# ProPrj__-__2025-12-04.net
KiCad netlist of a schematic drawn in EasyEDA Pro
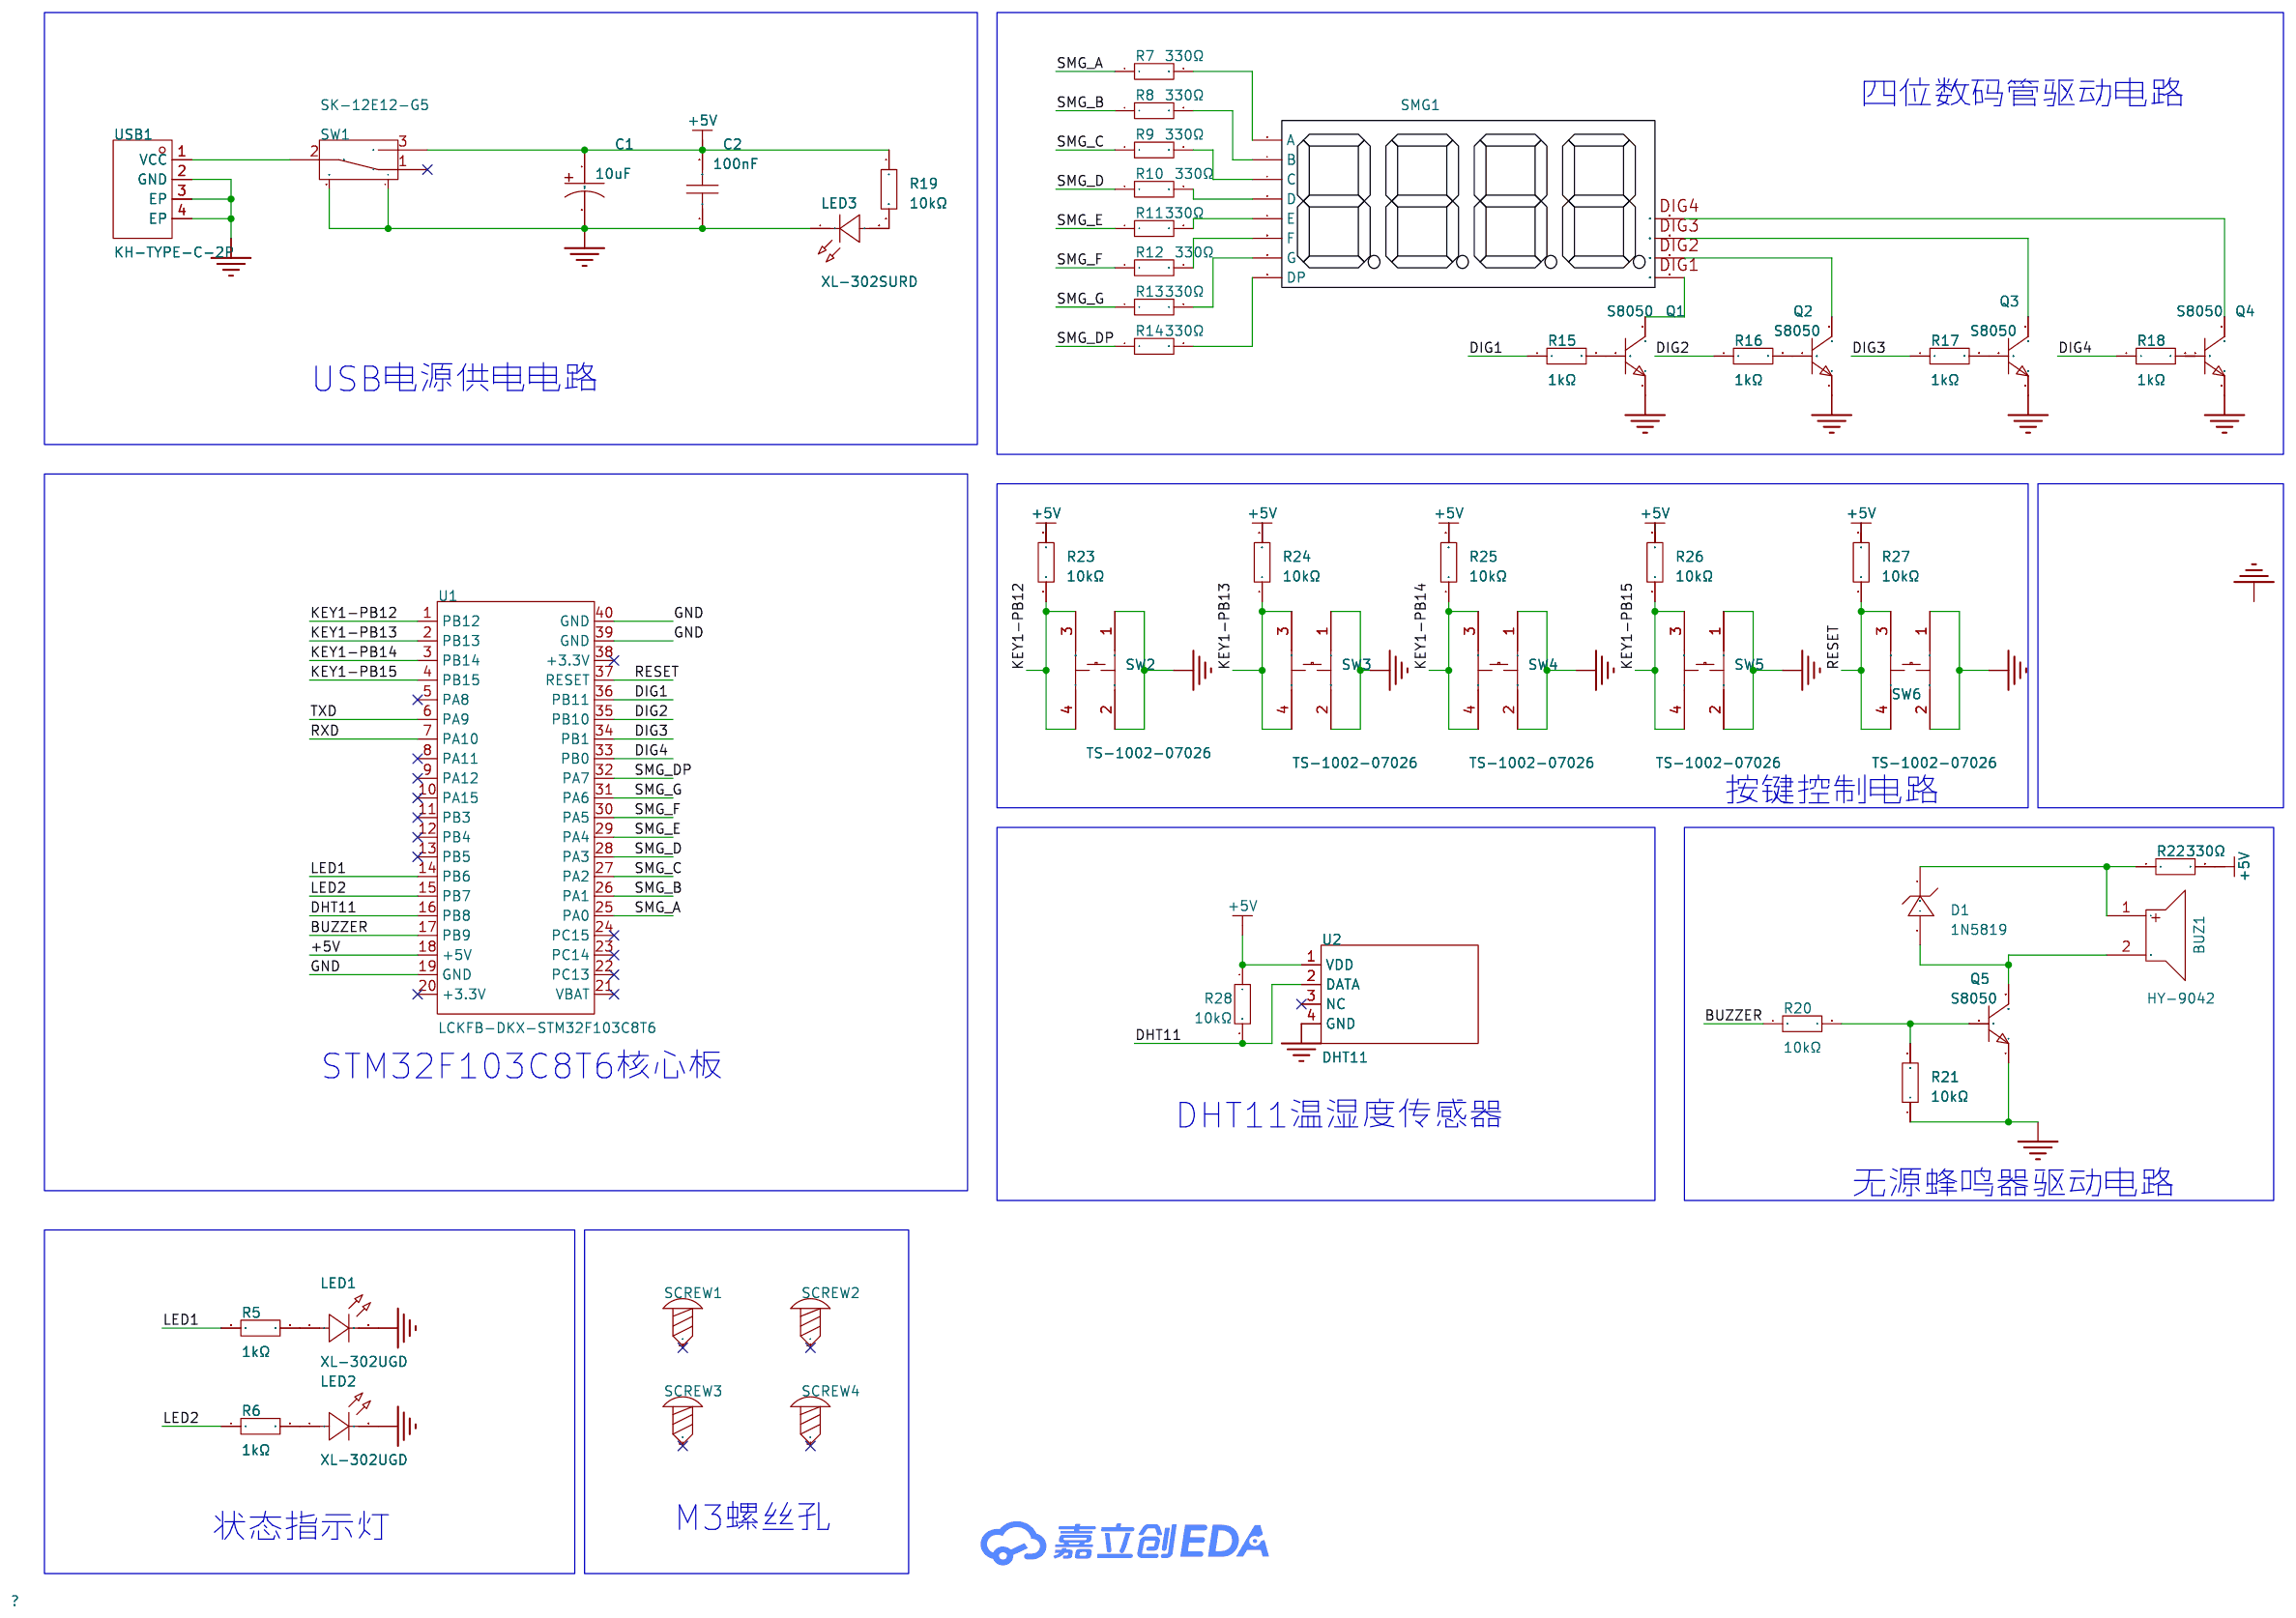
[diagram p0: schematic sheet]

(export (version "E")
  (design (tool "Eeschema 10.0.6"))
  (components
    (comp (ref "BUZ1")
      (value "HY-9042")
      (footprint "easyedapro:BUZ-TH_BD9.0-P4.00-D0.6-FD")
      (libsource (lib "easyedapro") (part "HY-9042"))
    )
    (comp (ref "C1")
      (value "10uF")
      (footprint "easyedapro:CAP-TH_BD4.0-P1.50-D0.8-FD")
      (description "容值:10uF;精度:±20%;额定电压:25V;")
      (fields
        (field (name "Manufacturer Part") "KF1E100MB050A00CV0")
        (field (name "Manufacturer") "HUAWEI(华威集团)")
      )
      (libsource (lib "easyedapro") (part "KF1E100MB050A00CV0"))
    )
    (comp (ref "C2")
      (value "100nF")
      (footprint "easyedapro:CAP-TH_L5.0-W2.5-P5.08-D0.7")
      (description "容值:100nF;精度:-20%~+80%;额定电压:50V;温度系数:Y5V;")
      (fields
        (field (name "Manufacturer Part") "CC1H104ZC74D3F5O30MN")
        (field (name "Manufacturer") "Dersonic(德尔创)")
      )
      (libsource (lib "easyedapro") (part "CC1H104ZC74D3F5O30MN"))
    )
    (comp (ref "D1")
      (value "1N5819")
      (footprint "easyedapro:DO-41_BD2.4-L4.7-P8.70-D0.9-RD")
      (description "二极管配置:独立式;正向压降(Vf):900mV@3A;直流反向耐压(Vr):40V;整流电流:1A;")
      (fields (field (name "Manufacturer") "LGE(鲁光)"))
      (libsource (lib "easyedapro") (part "1N5819_C402218"))
    )
    (comp (ref "LED1")
      (value "XL-302UGD")
      (footprint "easyedapro:LED-TH_BD3.8-P2.54-FD_GREEN")
      (fields (field (name "Manufacturer") "XINGLIGHT(成兴光)"))
      (libsource (lib "easyedapro") (part "XL-302UGD"))
    )
    (comp (ref "LED2")
      (value "XL-302UGD")
      (footprint "easyedapro:LED-TH_BD3.8-P2.54-FD_GREEN")
      (fields (field (name "Manufacturer") "XINGLIGHT(成兴光)"))
      (libsource (lib "easyedapro") (part "XL-302UGD"))
    )
    (comp (ref "LED3")
      (value "XL-302SURD")
      (footprint "easyedapro:LED-TH_BD3.8-P2.54-RD")
      (fields (field (name "Manufacturer") "XINGLIGHT(成兴光)"))
      (libsource (lib "easyedapro") (part "XL-302SURD"))
    )
    (comp (ref "Q1")
      (value "S8050")
      (footprint "easyedapro:TO-92-3_L4.5-W3.5-P1.27-L")
      (description "晶体管类型:NPN;集电极电流(Ic):500mA;集射极击穿电压(Vceo):25V;耗散功率(Pd):625mW;直流电流增益(hFE):160@50mA,1V;")
      (fields (field (name "Manufacturer") "JSMSEMI(杰盛微)"))
      (libsource (lib "easyedapro") (part "S8050_C2931492"))
    )
    (comp (ref "Q2")
      (value "S8050")
      (footprint "easyedapro:TO-92-3_L4.5-W3.5-P1.27-L")
      (description "晶体管类型:NPN;集电极电流(Ic):500mA;集射极击穿电压(Vceo):25V;耗散功率(Pd):625mW;直流电流增益(hFE):160@50mA,1V;")
      (fields (field (name "Manufacturer") "JSMSEMI(杰盛微)"))
      (libsource (lib "easyedapro") (part "S8050_C2931492"))
    )
    (comp (ref "Q3")
      (value "S8050")
      (footprint "easyedapro:TO-92-3_L4.5-W3.5-P1.27-L")
      (description "晶体管类型:NPN;集电极电流(Ic):500mA;集射极击穿电压(Vceo):25V;耗散功率(Pd):625mW;直流电流增益(hFE):160@50mA,1V;")
      (fields (field (name "Manufacturer") "JSMSEMI(杰盛微)"))
      (libsource (lib "easyedapro") (part "S8050_C2931492"))
    )
    (comp (ref "Q4")
      (value "S8050")
      (footprint "easyedapro:TO-92-3_L4.5-W3.5-P1.27-L")
      (description "晶体管类型:NPN;集电极电流(Ic):500mA;集射极击穿电压(Vceo):25V;耗散功率(Pd):625mW;直流电流增益(hFE):160@50mA,1V;")
      (fields (field (name "Manufacturer") "JSMSEMI(杰盛微)"))
      (libsource (lib "easyedapro") (part "S8050_C2931492"))
    )
    (comp (ref "Q5")
      (value "S8050")
      (footprint "easyedapro:TO-92-3_L4.5-W3.5-P1.27-L")
      (description "晶体管类型:NPN;集电极电流(Ic):500mA;集射极击穿电压(Vceo):25V;耗散功率(Pd):625mW;直流电流增益(hFE):160@50mA,1V;")
      (fields (field (name "Manufacturer") "JSMSEMI(杰盛微)"))
      (libsource (lib "easyedapro") (part "S8050_C2931492"))
    )
    (comp (ref "R5")
      (value "1kΩ")
      (footprint "easyedapro:RES-TH_BD2.2-L6.5-P10.50-D0.6")
      (description "电阻类型:金属膜电阻;阻值:1kΩ;精度:±5%;功率:250mW;")
      (fields (field (name "Manufacturer Part") "MFR-25JT-52-1K") (field (name "Manufacturer") "YAGEO(国巨)"))
      (libsource (lib "easyedapro") (part "MFR-25JT-52-1K"))
    )
    (comp (ref "R6")
      (value "1kΩ")
      (footprint "easyedapro:RES-TH_BD2.2-L6.5-P10.50-D0.6")
      (description "电阻类型:金属膜电阻;阻值:1kΩ;精度:±5%;功率:250mW;")
      (fields (field (name "Manufacturer Part") "MFR-25JT-52-1K") (field (name "Manufacturer") "YAGEO(国巨)"))
      (libsource (lib "easyedapro") (part "MFR-25JT-52-1K"))
    )
    (comp (ref "R7")
      (value "330Ω")
      (footprint "easyedapro:RES-TH_BD2.2-L6.5-P10.50-D0.6")
      (description "电阻类型:金属膜电阻;阻值:330Ω;精度:±1%;功率:250mW;温度系数:±50ppm/°C;")
      (fields (field (name "Manufacturer Part") "MFR-25FTE52-330R") (field (name "Manufacturer") "YAGEO(国巨)"))
      (libsource (lib "easyedapro") (part "MFR-25FTE52-330R"))
    )
    (comp (ref "R8")
      (value "330Ω")
      (footprint "easyedapro:RES-TH_BD2.2-L6.5-P10.50-D0.6")
      (description "电阻类型:金属膜电阻;阻值:330Ω;精度:±1%;功率:250mW;温度系数:±50ppm/°C;")
      (fields (field (name "Manufacturer Part") "MFR-25FTE52-330R") (field (name "Manufacturer") "YAGEO(国巨)"))
      (libsource (lib "easyedapro") (part "MFR-25FTE52-330R"))
    )
    (comp (ref "R9")
      (value "330Ω")
      (footprint "easyedapro:RES-TH_BD2.2-L6.5-P10.50-D0.6")
      (description "电阻类型:金属膜电阻;阻值:330Ω;精度:±1%;功率:250mW;温度系数:±50ppm/°C;")
      (fields (field (name "Manufacturer Part") "MFR-25FTE52-330R") (field (name "Manufacturer") "YAGEO(国巨)"))
      (libsource (lib "easyedapro") (part "MFR-25FTE52-330R"))
    )
    (comp (ref "R10")
      (value "330Ω")
      (footprint "easyedapro:RES-TH_BD2.2-L6.5-P10.50-D0.6")
      (description "电阻类型:金属膜电阻;阻值:330Ω;精度:±1%;功率:250mW;温度系数:±50ppm/°C;")
      (fields (field (name "Manufacturer Part") "MFR-25FTE52-330R") (field (name "Manufacturer") "YAGEO(国巨)"))
      (libsource (lib "easyedapro") (part "MFR-25FTE52-330R"))
    )
    (comp (ref "R11")
      (value "330Ω")
      (footprint "easyedapro:RES-TH_BD2.2-L6.5-P10.50-D0.6")
      (description "电阻类型:金属膜电阻;阻值:330Ω;精度:±1%;功率:250mW;温度系数:±50ppm/°C;")
      (fields (field (name "Manufacturer Part") "MFR-25FTE52-330R") (field (name "Manufacturer") "YAGEO(国巨)"))
      (libsource (lib "easyedapro") (part "MFR-25FTE52-330R"))
    )
    (comp (ref "R12")
      (value "330Ω")
      (footprint "easyedapro:RES-TH_BD2.2-L6.5-P10.50-D0.6")
      (description "电阻类型:金属膜电阻;阻值:330Ω;精度:±1%;功率:250mW;温度系数:±50ppm/°C;")
      (fields (field (name "Manufacturer Part") "MFR-25FTE52-330R") (field (name "Manufacturer") "YAGEO(国巨)"))
      (libsource (lib "easyedapro") (part "MFR-25FTE52-330R"))
    )
    (comp (ref "R13")
      (value "330Ω")
      (footprint "easyedapro:RES-TH_BD2.2-L6.5-P10.50-D0.6")
      (description "电阻类型:金属膜电阻;阻值:330Ω;精度:±1%;功率:250mW;温度系数:±50ppm/°C;")
      (fields (field (name "Manufacturer Part") "MFR-25FTE52-330R") (field (name "Manufacturer") "YAGEO(国巨)"))
      (libsource (lib "easyedapro") (part "MFR-25FTE52-330R"))
    )
    (comp (ref "R14")
      (value "330Ω")
      (footprint "easyedapro:RES-TH_BD2.2-L6.5-P10.50-D0.6")
      (description "电阻类型:金属膜电阻;阻值:330Ω;精度:±1%;功率:250mW;温度系数:±50ppm/°C;")
      (fields (field (name "Manufacturer Part") "MFR-25FTE52-330R") (field (name "Manufacturer") "YAGEO(国巨)"))
      (libsource (lib "easyedapro") (part "MFR-25FTE52-330R"))
    )
    (comp (ref "R15")
      (value "1kΩ")
      (footprint "easyedapro:RES-TH_BD2.2-L6.5-P10.50-D0.6")
      (description "电阻类型:金属膜电阻;阻值:1kΩ;精度:±5%;功率:250mW;")
      (fields (field (name "Manufacturer Part") "MFR-25JT-52-1K") (field (name "Manufacturer") "YAGEO(国巨)"))
      (libsource (lib "easyedapro") (part "MFR-25JT-52-1K"))
    )
    (comp (ref "R16")
      (value "1kΩ")
      (footprint "easyedapro:RES-TH_BD2.2-L6.5-P10.50-D0.6")
      (description "电阻类型:金属膜电阻;阻值:1kΩ;精度:±5%;功率:250mW;")
      (fields (field (name "Manufacturer Part") "MFR-25JT-52-1K") (field (name "Manufacturer") "YAGEO(国巨)"))
      (libsource (lib "easyedapro") (part "MFR-25JT-52-1K"))
    )
    (comp (ref "R17")
      (value "1kΩ")
      (footprint "easyedapro:RES-TH_BD2.2-L6.5-P10.50-D0.6")
      (description "电阻类型:金属膜电阻;阻值:1kΩ;精度:±5%;功率:250mW;")
      (fields (field (name "Manufacturer Part") "MFR-25JT-52-1K") (field (name "Manufacturer") "YAGEO(国巨)"))
      (libsource (lib "easyedapro") (part "MFR-25JT-52-1K"))
    )
    (comp (ref "R18")
      (value "1kΩ")
      (footprint "easyedapro:RES-TH_BD2.2-L6.5-P10.50-D0.6")
      (description "电阻类型:金属膜电阻;阻值:1kΩ;精度:±5%;功率:250mW;")
      (fields (field (name "Manufacturer Part") "MFR-25JT-52-1K") (field (name "Manufacturer") "YAGEO(国巨)"))
      (libsource (lib "easyedapro") (part "MFR-25JT-52-1K"))
    )
    (comp (ref "R19")
      (value "10kΩ")
      (footprint "easyedapro:RES-TH_BD2.4-L6.3-P10.30-D0.6")
      (description "电阻类型:金属膜电阻;阻值:10kΩ;精度:±5%;功率:250mW;")
      (fields (field (name "Manufacturer Part") "MFR-25JT-52-10K") (field (name "Manufacturer") "YAGEO(国巨)"))
      (libsource (lib "easyedapro") (part "MFR-25JT-52-10K"))
    )
    (comp (ref "R20")
      (value "10kΩ")
      (footprint "easyedapro:RES-TH_BD2.4-L6.3-P10.30-D0.6")
      (description "电阻类型:金属膜电阻;阻值:10kΩ;精度:±5%;功率:250mW;")
      (fields (field (name "Manufacturer Part") "MFR-25JT-52-10K") (field (name "Manufacturer") "YAGEO(国巨)"))
      (libsource (lib "easyedapro") (part "MFR-25JT-52-10K"))
    )
    (comp (ref "R21")
      (value "10kΩ")
      (footprint "easyedapro:RES-TH_BD2.4-L6.3-P10.30-D0.6")
      (description "电阻类型:金属膜电阻;阻值:10kΩ;精度:±5%;功率:250mW;")
      (fields (field (name "Manufacturer Part") "MFR-25JT-52-10K") (field (name "Manufacturer") "YAGEO(国巨)"))
      (libsource (lib "easyedapro") (part "MFR-25JT-52-10K"))
    )
    (comp (ref "R22")
      (value "330Ω")
      (footprint "easyedapro:RES-TH_BD2.2-L6.5-P10.50-D0.6")
      (description "电阻类型:金属膜电阻;阻值:330Ω;精度:±1%;功率:250mW;温度系数:±50ppm/°C;")
      (fields (field (name "Manufacturer Part") "MFR-25FTE52-330R") (field (name "Manufacturer") "YAGEO(国巨)"))
      (libsource (lib "easyedapro") (part "MFR-25FTE52-330R"))
    )
    (comp (ref "R23")
      (value "10kΩ")
      (footprint "easyedapro:RES-TH_BD2.4-L6.3-P10.30-D0.6")
      (description "电阻类型:金属膜电阻;阻值:10kΩ;精度:±5%;功率:250mW;")
      (fields (field (name "Manufacturer Part") "MFR-25JT-52-10K") (field (name "Manufacturer") "YAGEO(国巨)"))
      (libsource (lib "easyedapro") (part "MFR-25JT-52-10K"))
    )
    (comp (ref "R24")
      (value "10kΩ")
      (footprint "easyedapro:RES-TH_BD2.4-L6.3-P10.30-D0.6")
      (description "电阻类型:金属膜电阻;阻值:10kΩ;精度:±5%;功率:250mW;")
      (fields (field (name "Manufacturer Part") "MFR-25JT-52-10K") (field (name "Manufacturer") "YAGEO(国巨)"))
      (libsource (lib "easyedapro") (part "MFR-25JT-52-10K"))
    )
    (comp (ref "R25")
      (value "10kΩ")
      (footprint "easyedapro:RES-TH_BD2.4-L6.3-P10.30-D0.6")
      (description "电阻类型:金属膜电阻;阻值:10kΩ;精度:±5%;功率:250mW;")
      (fields (field (name "Manufacturer Part") "MFR-25JT-52-10K") (field (name "Manufacturer") "YAGEO(国巨)"))
      (libsource (lib "easyedapro") (part "MFR-25JT-52-10K"))
    )
    (comp (ref "R26")
      (value "10kΩ")
      (footprint "easyedapro:RES-TH_BD2.4-L6.3-P10.30-D0.6")
      (description "电阻类型:金属膜电阻;阻值:10kΩ;精度:±5%;功率:250mW;")
      (fields (field (name "Manufacturer Part") "MFR-25JT-52-10K") (field (name "Manufacturer") "YAGEO(国巨)"))
      (libsource (lib "easyedapro") (part "MFR-25JT-52-10K"))
    )
    (comp (ref "R27")
      (value "10kΩ")
      (footprint "easyedapro:RES-TH_BD2.4-L6.3-P10.30-D0.6")
      (description "电阻类型:金属膜电阻;阻值:10kΩ;精度:±5%;功率:250mW;")
      (fields (field (name "Manufacturer Part") "MFR-25JT-52-10K") (field (name "Manufacturer") "YAGEO(国巨)"))
      (libsource (lib "easyedapro") (part "MFR-25JT-52-10K"))
    )
    (comp (ref "R28")
      (value "10kΩ")
      (footprint "easyedapro:RES-TH_BD2.4-L6.3-P10.30-D0.6")
      (description "电阻类型:金属膜电阻;阻值:10kΩ;精度:±5%;功率:250mW;")
      (fields (field (name "Manufacturer Part") "MFR-25JT-52-10K") (field (name "Manufacturer") "YAGEO(国巨)"))
      (libsource (lib "easyedapro") (part "MFR-25JT-52-10K"))
    )
    (comp (ref "SCREW1")
      (value "~")
      (footprint "easyedapro:M3螺丝")
      (libsource (lib "easyedapro") (part "螺丝孔"))
    )
    (comp (ref "SCREW2")
      (value "~")
      (footprint "easyedapro:M3螺丝")
      (libsource (lib "easyedapro") (part "螺丝孔"))
    )
    (comp (ref "SCREW3")
      (value "~")
      (footprint "easyedapro:M3螺丝")
      (libsource (lib "easyedapro") (part "螺丝孔"))
    )
    (comp (ref "SCREW4")
      (value "~")
      (footprint "easyedapro:M3螺丝")
      (libsource (lib "easyedapro") (part "螺丝孔"))
    )
    (comp (ref "SMG1")
      (value "~")
      (footprint "easyedapro:LED-SEG-TH_FJ5461AH")
      (libsource (lib "easyedapro") (part "LED_SEG_TH_0.56x4"))
    )
    (comp (ref "SW1")
      (value "SK-12E12-G5")
      (footprint "easyedapro:SW-TH_SK-12E12-G5")
      (description "电路结构:单刀双掷;安装方式:-;额定电流:-;额定电压:-;工作寿命:5千次;")
      (fields (field (name "Manufacturer") "韩国韩荣"))
      (libsource (lib "easyedapro") (part "SK-12E12-G5"))
    )
    (comp (ref "SW2")
      (value "TS-1002-07026")
      (footprint "easyedapro:SW-TH_4P-L6.0-W6.0-P4.50-LS6.5")
      (description "电路结构:单刀单掷;按钮形状:圆形按钮;安装方式:直插;开关长度:6mm;开关宽度:6mm;开关高度:7mm;触点电流:50mA;额定电压:12V;带灯:-;工作寿命:-;")
      (fields (field (name "Manufacturer") "XUNPU(讯普)"))
      (libsource (lib "easyedapro") (part "TS-1002-07026"))
    )
    (comp (ref "SW3")
      (value "TS-1002-07026")
      (footprint "easyedapro:SW-TH_4P-L6.0-W6.0-P4.50-LS6.5")
      (description "电路结构:单刀单掷;按钮形状:圆形按钮;安装方式:直插;开关长度:6mm;开关宽度:6mm;开关高度:7mm;触点电流:50mA;额定电压:12V;带灯:-;工作寿命:-;")
      (fields (field (name "Manufacturer") "XUNPU(讯普)"))
      (libsource (lib "easyedapro") (part "TS-1002-07026"))
    )
    (comp (ref "SW4")
      (value "TS-1002-07026")
      (footprint "easyedapro:SW-TH_4P-L6.0-W6.0-P4.50-LS6.5")
      (description "电路结构:单刀单掷;按钮形状:圆形按钮;安装方式:直插;开关长度:6mm;开关宽度:6mm;开关高度:7mm;触点电流:50mA;额定电压:12V;带灯:-;工作寿命:-;")
      (fields (field (name "Manufacturer") "XUNPU(讯普)"))
      (libsource (lib "easyedapro") (part "TS-1002-07026"))
    )
    (comp (ref "SW5")
      (value "TS-1002-07026")
      (footprint "easyedapro:SW-TH_4P-L6.0-W6.0-P4.50-LS6.5")
      (description "电路结构:单刀单掷;按钮形状:圆形按钮;安装方式:直插;开关长度:6mm;开关宽度:6mm;开关高度:7mm;触点电流:50mA;额定电压:12V;带灯:-;工作寿命:-;")
      (fields (field (name "Manufacturer") "XUNPU(讯普)"))
      (libsource (lib "easyedapro") (part "TS-1002-07026"))
    )
    (comp (ref "SW6")
      (value "TS-1002-07026")
      (footprint "easyedapro:SW-TH_4P-L6.0-W6.0-P4.50-LS6.5")
      (description "电路结构:单刀单掷;按钮形状:圆形按钮;安装方式:直插;开关长度:6mm;开关宽度:6mm;开关高度:7mm;触点电流:50mA;额定电压:12V;带灯:-;工作寿命:-;")
      (fields (field (name "Manufacturer") "XUNPU(讯普)"))
      (libsource (lib "easyedapro") (part "TS-1002-07026"))
    )
    (comp (ref "U1")
      (value "LCKFB-DKX-STM32F103C8T6")
      (footprint "easyedapro:CONN-TH_L53.3-W22.9_STM32F103C8T6-CARD")
      (fields (field (name "Manufacturer") "立创开发板"))
      (libsource (lib "easyedapro") (part "LCKFB-DKX-STM32F103C8T6"))
    )
    (comp (ref "U2")
      (value "DHT11")
      (footprint "easyedapro:SENSOR-TH_DHT11")
      (description "新款电容式数字温湿度传感器,老款已停产16.1x12.6x5.8mm")
      (fields (field (name "Manufacturer") "广州奥松"))
      (libsource (lib "easyedapro") (part "DHT11"))
    )
    (comp (ref "USB1")
      (value "KH-TYPE-C-2P")
      (footprint "easyedapro:USB-SMD_KH-TYPE-C-2P")
      (description "连接器类型:Type-C;协议标准:-;公母:-;安装方式:-;触点数量:2P;端口数量:-;额定电流 - 电源:-;工作温度:-;")
      (fields (field (name "Manufacturer") "kinghelm(金航标)"))
      (libsource (lib "easyedapro") (part "KH-TYPE-C-2P"))
    )
  )
  (nets
    (net (code "1") (name "+5V") (class "Default")
      (node (ref "C1") (pin "1") (pinfunction "1_1") (pintype "unspecified"))
      (node (ref "C2") (pin "2") (pinfunction "2_2") (pintype "unspecified"))
      (node (ref "R19") (pin "1") (pinfunction "1_1") (pintype "unspecified"))
      (node (ref "R22") (pin "2") (pinfunction "2_2") (pintype "input"))
      (node (ref "R23") (pin "2") (pinfunction "2_2") (pintype "unspecified"))
      (node (ref "R24") (pin "2") (pinfunction "2_2") (pintype "unspecified"))
      (node (ref "R25") (pin "2") (pinfunction "2_2") (pintype "unspecified"))
      (node (ref "R26") (pin "2") (pinfunction "2_2") (pintype "unspecified"))
      (node (ref "R27") (pin "2") (pinfunction "2_2") (pintype "unspecified"))
      (node (ref "R28") (pin "1") (pinfunction "1_1") (pintype "unspecified"))
      (node (ref "SW1") (pin "3") (pinfunction "3_3") (pintype "unspecified"))
      (node (ref "U1") (pin "18") (pinfunction "+5V_18") (pintype "unspecified"))
      (node (ref "U2") (pin "1") (pinfunction "VDD_1") (pintype "unspecified"))
    )
    (net (code "2") (name "/BUZZER") (class "Default")
      (node (ref "R20") (pin "1") (pinfunction "1_1") (pintype "unspecified"))
      (node (ref "U1") (pin "17") (pinfunction "PB9_17") (pintype "unspecified"))
    )
    (net (code "3") (name "/DHT11") (class "Default")
      (node (ref "R28") (pin "2") (pinfunction "2_2") (pintype "unspecified"))
      (node (ref "U1") (pin "16") (pinfunction "PB8_16") (pintype "unspecified"))
      (node (ref "U2") (pin "2") (pinfunction "DATA_2") (pintype "unspecified"))
    )
    (net (code "4") (name "/DIG1") (class "Default")
      (node (ref "R15") (pin "1") (pinfunction "1_1") (pintype "unspecified"))
      (node (ref "U1") (pin "36") (pinfunction "PB11_36") (pintype "unspecified"))
    )
    (net (code "5") (name "/DIG2") (class "Default")
      (node (ref "R16") (pin "1") (pinfunction "1_1") (pintype "unspecified"))
      (node (ref "U1") (pin "35") (pinfunction "PB10_35") (pintype "unspecified"))
    )
    (net (code "6") (name "/DIG3") (class "Default")
      (node (ref "R17") (pin "1") (pinfunction "1_1") (pintype "unspecified"))
      (node (ref "U1") (pin "34") (pinfunction "PB1_34") (pintype "unspecified"))
    )
    (net (code "7") (name "/DIG4") (class "Default")
      (node (ref "R18") (pin "1") (pinfunction "1_1") (pintype "unspecified"))
      (node (ref "U1") (pin "33") (pinfunction "PB0_33") (pintype "unspecified"))
    )
    (net (code "8") (name "/KEY1-PB12") (class "Default")
      (node (ref "R23") (pin "1") (pinfunction "1_1") (pintype "unspecified"))
      (node (ref "SW2") (pin "3") (pinfunction "3_3") (pintype "unspecified"))
      (node (ref "SW2") (pin "4") (pinfunction "4_4") (pintype "unspecified"))
      (node (ref "U1") (pin "1") (pinfunction "PB12_1") (pintype "unspecified"))
    )
    (net (code "9") (name "/KEY1-PB13") (class "Default")
      (node (ref "R24") (pin "1") (pinfunction "1_1") (pintype "unspecified"))
      (node (ref "SW3") (pin "3") (pinfunction "3_3") (pintype "unspecified"))
      (node (ref "SW3") (pin "4") (pinfunction "4_4") (pintype "unspecified"))
      (node (ref "U1") (pin "2") (pinfunction "PB13_2") (pintype "unspecified"))
    )
    (net (code "10") (name "/KEY1-PB14") (class "Default")
      (node (ref "R25") (pin "1") (pinfunction "1_1") (pintype "unspecified"))
      (node (ref "SW4") (pin "3") (pinfunction "3_3") (pintype "unspecified"))
      (node (ref "SW4") (pin "4") (pinfunction "4_4") (pintype "unspecified"))
      (node (ref "U1") (pin "3") (pinfunction "PB14_3") (pintype "unspecified"))
    )
    (net (code "11") (name "/KEY1-PB15") (class "Default")
      (node (ref "R26") (pin "1") (pinfunction "1_1") (pintype "unspecified"))
      (node (ref "SW5") (pin "3") (pinfunction "3_3") (pintype "unspecified"))
      (node (ref "SW5") (pin "4") (pinfunction "4_4") (pintype "unspecified"))
      (node (ref "U1") (pin "4") (pinfunction "PB15_4") (pintype "unspecified"))
    )
    (net (code "12") (name "/LED1") (class "Default")
      (node (ref "R5") (pin "1") (pinfunction "1_1") (pintype "unspecified"))
      (node (ref "U1") (pin "14") (pinfunction "PB6_14") (pintype "unspecified"))
    )
    (net (code "13") (name "/LED2") (class "Default")
      (node (ref "R6") (pin "1") (pinfunction "1_1") (pintype "unspecified"))
      (node (ref "U1") (pin "15") (pinfunction "PB7_15") (pintype "unspecified"))
    )
    (net (code "14") (name "/RESET") (class "Default")
      (node (ref "R27") (pin "1") (pinfunction "1_1") (pintype "unspecified"))
      (node (ref "SW6") (pin "3") (pinfunction "3_3") (pintype "unspecified"))
      (node (ref "SW6") (pin "4") (pinfunction "4_4") (pintype "unspecified"))
      (node (ref "U1") (pin "37") (pinfunction "RESET_37") (pintype "unspecified"))
    )
    (net (code "15") (name "/RXD") (class "Default")
      (node (ref "U1") (pin "7") (pinfunction "PA10_7") (pintype "unspecified"))
    )
    (net (code "16") (name "/SMG_A") (class "Default")
      (node (ref "R7") (pin "1") (pinfunction "1_1") (pintype "input"))
      (node (ref "U1") (pin "25") (pinfunction "PA0_25") (pintype "unspecified"))
    )
    (net (code "17") (name "/SMG_B") (class "Default")
      (node (ref "R8") (pin "1") (pinfunction "1_1") (pintype "input"))
      (node (ref "U1") (pin "26") (pinfunction "PA1_26") (pintype "unspecified"))
    )
    (net (code "18") (name "/SMG_C") (class "Default")
      (node (ref "R9") (pin "1") (pinfunction "1_1") (pintype "input"))
      (node (ref "U1") (pin "27") (pinfunction "PA2_27") (pintype "unspecified"))
    )
    (net (code "19") (name "/SMG_D") (class "Default")
      (node (ref "R10") (pin "1") (pinfunction "1_1") (pintype "input"))
      (node (ref "U1") (pin "28") (pinfunction "PA3_28") (pintype "unspecified"))
    )
    (net (code "20") (name "/SMG_DP") (class "Default")
      (node (ref "R14") (pin "1") (pinfunction "1_1") (pintype "input"))
      (node (ref "U1") (pin "32") (pinfunction "PA7_32") (pintype "unspecified"))
    )
    (net (code "21") (name "/SMG_E") (class "Default")
      (node (ref "R11") (pin "1") (pinfunction "1_1") (pintype "input"))
      (node (ref "U1") (pin "29") (pinfunction "PA4_29") (pintype "unspecified"))
    )
    (net (code "22") (name "/SMG_F") (class "Default")
      (node (ref "R12") (pin "1") (pinfunction "1_1") (pintype "input"))
      (node (ref "U1") (pin "30") (pinfunction "PA5_30") (pintype "unspecified"))
    )
    (net (code "23") (name "/SMG_G") (class "Default")
      (node (ref "R13") (pin "1") (pinfunction "1_1") (pintype "input"))
      (node (ref "U1") (pin "31") (pinfunction "PA6_31") (pintype "unspecified"))
    )
    (net (code "24") (name "/TXD") (class "Default")
      (node (ref "U1") (pin "6") (pinfunction "PA9_6") (pintype "unspecified"))
    )
    (net (code "25") (name "GND") (class "Default")
      (node (ref "C1") (pin "2") (pinfunction "2_2") (pintype "unspecified"))
      (node (ref "C2") (pin "1") (pinfunction "1_1") (pintype "unspecified"))
      (node (ref "LED1") (pin "2") (pinfunction "K_2") (pintype "unspecified"))
      (node (ref "LED2") (pin "2") (pinfunction "K_2") (pintype "unspecified"))
      (node (ref "LED3") (pin "1") (pinfunction "K_1") (pintype "unspecified"))
      (node (ref "Q1") (pin "1") (pinfunction "E_1") (pintype "unspecified"))
      (node (ref "Q2") (pin "1") (pinfunction "E_1") (pintype "unspecified"))
      (node (ref "Q3") (pin "1") (pinfunction "E_1") (pintype "unspecified"))
      (node (ref "Q4") (pin "1") (pinfunction "E_1") (pintype "unspecified"))
      (node (ref "Q5") (pin "1") (pinfunction "E_1") (pintype "unspecified"))
      (node (ref "R21") (pin "1") (pinfunction "1_1") (pintype "unspecified"))
      (node (ref "SW1") (pin "4") (pinfunction "4_4") (pintype "unspecified"))
      (node (ref "SW1") (pin "5") (pinfunction "5_5") (pintype "unspecified"))
      (node (ref "SW2") (pin "1") (pinfunction "1_1") (pintype "unspecified"))
      (node (ref "SW2") (pin "2") (pinfunction "2_2") (pintype "unspecified"))
      (node (ref "SW3") (pin "1") (pinfunction "1_1") (pintype "unspecified"))
      (node (ref "SW3") (pin "2") (pinfunction "2_2") (pintype "unspecified"))
      (node (ref "SW4") (pin "1") (pinfunction "1_1") (pintype "unspecified"))
      (node (ref "SW4") (pin "2") (pinfunction "2_2") (pintype "unspecified"))
      (node (ref "SW5") (pin "1") (pinfunction "1_1") (pintype "unspecified"))
      (node (ref "SW5") (pin "2") (pinfunction "2_2") (pintype "unspecified"))
      (node (ref "SW6") (pin "1") (pinfunction "1_1") (pintype "unspecified"))
      (node (ref "SW6") (pin "2") (pinfunction "2_2") (pintype "unspecified"))
      (node (ref "U1") (pin "19") (pinfunction "GND_19") (pintype "unspecified"))
      (node (ref "U1") (pin "39") (pinfunction "GND_39") (pintype "unspecified"))
      (node (ref "U1") (pin "40") (pinfunction "GND_40") (pintype "unspecified"))
      (node (ref "U2") (pin "4") (pinfunction "GND_4") (pintype "unspecified"))
      (node (ref "USB1") (pin "2") (pinfunction "GND_2") (pintype "unspecified"))
      (node (ref "USB1") (pin "3") (pinfunction "EP_3") (pintype "unspecified"))
      (node (ref "USB1") (pin "4") (pinfunction "EP_4") (pintype "unspecified"))
    )
    (net (code "26") (name "Net-(D1-A)") (class "Default")
      (node (ref "BUZ1") (pin "2") (pinfunction "2_2") (pintype "unspecified"))
      (node (ref "D1") (pin "2") (pinfunction "A_2") (pintype "unspecified"))
      (node (ref "Q5") (pin "3") (pinfunction "C_3") (pintype "unspecified"))
    )
    (net (code "27") (name "Net-(D1-C)") (class "Default")
      (node (ref "BUZ1") (pin "1") (pinfunction "1_1") (pintype "unspecified"))
      (node (ref "D1") (pin "1") (pinfunction "C_1") (pintype "unspecified"))
      (node (ref "R22") (pin "1") (pinfunction "1_1") (pintype "input"))
    )
    (net (code "28") (name "Net-(LED1-A)") (class "Default")
      (node (ref "LED1") (pin "1") (pinfunction "A_1") (pintype "unspecified"))
      (node (ref "R5") (pin "2") (pinfunction "2_2") (pintype "unspecified"))
    )
    (net (code "29") (name "Net-(LED2-A)") (class "Default")
      (node (ref "LED2") (pin "1") (pinfunction "A_1") (pintype "unspecified"))
      (node (ref "R6") (pin "2") (pinfunction "2_2") (pintype "unspecified"))
    )
    (net (code "30") (name "Net-(LED3-A)") (class "Default")
      (node (ref "LED3") (pin "2") (pinfunction "A_2") (pintype "unspecified"))
      (node (ref "R19") (pin "2") (pinfunction "2_2") (pintype "unspecified"))
    )
    (net (code "31") (name "Net-(Q1-B)") (class "Default")
      (node (ref "Q1") (pin "2") (pinfunction "B_2") (pintype "unspecified"))
      (node (ref "R15") (pin "2") (pinfunction "2_2") (pintype "unspecified"))
    )
    (net (code "32") (name "Net-(Q1-C)") (class "Default")
      (node (ref "Q1") (pin "3") (pinfunction "C_3") (pintype "unspecified"))
      (node (ref "SMG1") (pin "12") (pinfunction "DIG1_12") (pintype "input"))
    )
    (net (code "33") (name "Net-(Q2-B)") (class "Default")
      (node (ref "Q2") (pin "2") (pinfunction "B_2") (pintype "unspecified"))
      (node (ref "R16") (pin "2") (pinfunction "2_2") (pintype "unspecified"))
    )
    (net (code "34") (name "Net-(Q2-C)") (class "Default")
      (node (ref "Q2") (pin "3") (pinfunction "C_3") (pintype "unspecified"))
      (node (ref "SMG1") (pin "9") (pinfunction "DIG2_9") (pintype "input"))
    )
    (net (code "35") (name "Net-(Q3-B)") (class "Default")
      (node (ref "Q3") (pin "2") (pinfunction "B_2") (pintype "unspecified"))
      (node (ref "R17") (pin "2") (pinfunction "2_2") (pintype "unspecified"))
    )
    (net (code "36") (name "Net-(Q3-C)") (class "Default")
      (node (ref "Q3") (pin "3") (pinfunction "C_3") (pintype "unspecified"))
      (node (ref "SMG1") (pin "8") (pinfunction "DIG3_8") (pintype "input"))
    )
    (net (code "37") (name "Net-(Q4-B)") (class "Default")
      (node (ref "Q4") (pin "2") (pinfunction "B_2") (pintype "unspecified"))
      (node (ref "R18") (pin "2") (pinfunction "2_2") (pintype "unspecified"))
    )
    (net (code "38") (name "Net-(Q4-C)") (class "Default")
      (node (ref "Q4") (pin "3") (pinfunction "C_3") (pintype "unspecified"))
      (node (ref "SMG1") (pin "6") (pinfunction "DIG4_6") (pintype "input"))
    )
    (net (code "39") (name "Net-(Q5-B)") (class "Default")
      (node (ref "Q5") (pin "2") (pinfunction "B_2") (pintype "unspecified"))
      (node (ref "R20") (pin "2") (pinfunction "2_2") (pintype "unspecified"))
      (node (ref "R21") (pin "2") (pinfunction "2_2") (pintype "unspecified"))
    )
    (net (code "40") (name "Net-(SMG1-A)") (class "Default")
      (node (ref "R7") (pin "2") (pinfunction "2_2") (pintype "input"))
      (node (ref "SMG1") (pin "11") (pinfunction "A_11") (pintype "input"))
    )
    (net (code "41") (name "Net-(SMG1-B)") (class "Default")
      (node (ref "R8") (pin "2") (pinfunction "2_2") (pintype "input"))
      (node (ref "SMG1") (pin "7") (pinfunction "B_7") (pintype "input"))
    )
    (net (code "42") (name "Net-(SMG1-C)") (class "Default")
      (node (ref "R9") (pin "2") (pinfunction "2_2") (pintype "input"))
      (node (ref "SMG1") (pin "4") (pinfunction "C_4") (pintype "input"))
    )
    (net (code "43") (name "Net-(SMG1-D)") (class "Default")
      (node (ref "R10") (pin "2") (pinfunction "2_2") (pintype "input"))
      (node (ref "SMG1") (pin "2") (pinfunction "D_2") (pintype "input"))
    )
    (net (code "44") (name "Net-(SMG1-DP)") (class "Default")
      (node (ref "R14") (pin "2") (pinfunction "2_2") (pintype "input"))
      (node (ref "SMG1") (pin "3") (pinfunction "DP_3") (pintype "input"))
    )
    (net (code "45") (name "Net-(SMG1-E)") (class "Default")
      (node (ref "R11") (pin "2") (pinfunction "2_2") (pintype "input"))
      (node (ref "SMG1") (pin "1") (pinfunction "E_1") (pintype "input"))
    )
    (net (code "46") (name "Net-(SMG1-F)") (class "Default")
      (node (ref "R12") (pin "2") (pinfunction "2_2") (pintype "input"))
      (node (ref "SMG1") (pin "10") (pinfunction "F_10") (pintype "input"))
    )
    (net (code "47") (name "Net-(SMG1-G)") (class "Default")
      (node (ref "R13") (pin "2") (pinfunction "2_2") (pintype "input"))
      (node (ref "SMG1") (pin "5") (pinfunction "G_5") (pintype "input"))
    )
    (net (code "48") (name "Net-(USB1-VCC)") (class "Default")
      (node (ref "SW1") (pin "2") (pinfunction "2_2") (pintype "unspecified"))
      (node (ref "USB1") (pin "1") (pinfunction "VCC_1") (pintype "unspecified"))
    )
    (net (code "49") (name "unconnected-(SCREW1-Pad1)") (class "Default")
      (node (ref "SCREW1") (pin "1") (pinfunction "1_1") (pintype "input+no_connect"))
    )
    (net (code "50") (name "unconnected-(SCREW2-Pad1)") (class "Default")
      (node (ref "SCREW2") (pin "1") (pinfunction "1_1") (pintype "input+no_connect"))
    )
    (net (code "51") (name "unconnected-(SCREW3-Pad1)") (class "Default")
      (node (ref "SCREW3") (pin "1") (pinfunction "1_1") (pintype "input+no_connect"))
    )
    (net (code "52") (name "unconnected-(SCREW4-Pad1)") (class "Default")
      (node (ref "SCREW4") (pin "1") (pinfunction "1_1") (pintype "input+no_connect"))
    )
    (net (code "53") (name "unconnected-(SW1-Pad1)") (class "Default")
      (node (ref "SW1") (pin "1") (pinfunction "1_1") (pintype "unspecified+no_connect"))
    )
    (net (code "54") (name "unconnected-(U1-+3.3V-Pad20)") (class "Default")
      (node (ref "U1") (pin "20") (pinfunction "+3.3V_20") (pintype "unspecified+no_connect"))
    )
    (net (code "55") (name "unconnected-(U1-+3.3V-Pad38)") (class "Default")
      (node (ref "U1") (pin "38") (pinfunction "+3.3V_38") (pintype "unspecified+no_connect"))
    )
    (net (code "56") (name "unconnected-(U1-PA8-Pad5)") (class "Default")
      (node (ref "U1") (pin "5") (pinfunction "PA8_5") (pintype "unspecified+no_connect"))
    )
    (net (code "57") (name "unconnected-(U1-PA11-Pad8)") (class "Default")
      (node (ref "U1") (pin "8") (pinfunction "PA11_8") (pintype "unspecified+no_connect"))
    )
    (net (code "58") (name "unconnected-(U1-PA12-Pad9)") (class "Default")
      (node (ref "U1") (pin "9") (pinfunction "PA12_9") (pintype "unspecified+no_connect"))
    )
    (net (code "59") (name "unconnected-(U1-PA15-Pad10)") (class "Default")
      (node (ref "U1") (pin "10") (pinfunction "PA15_10") (pintype "unspecified+no_connect"))
    )
    (net (code "60") (name "unconnected-(U1-PB3-Pad11)") (class "Default")
      (node (ref "U1") (pin "11") (pinfunction "PB3_11") (pintype "unspecified+no_connect"))
    )
    (net (code "61") (name "unconnected-(U1-PB4-Pad12)") (class "Default")
      (node (ref "U1") (pin "12") (pinfunction "PB4_12") (pintype "unspecified+no_connect"))
    )
    (net (code "62") (name "unconnected-(U1-PB5-Pad13)") (class "Default")
      (node (ref "U1") (pin "13") (pinfunction "PB5_13") (pintype "unspecified+no_connect"))
    )
    (net (code "63") (name "unconnected-(U1-PC13-Pad22)") (class "Default")
      (node (ref "U1") (pin "22") (pinfunction "PC13_22") (pintype "unspecified+no_connect"))
    )
    (net (code "64") (name "unconnected-(U1-PC14-Pad23)") (class "Default")
      (node (ref "U1") (pin "23") (pinfunction "PC14_23") (pintype "unspecified+no_connect"))
    )
    (net (code "65") (name "unconnected-(U1-PC15-Pad24)") (class "Default")
      (node (ref "U1") (pin "24") (pinfunction "PC15_24") (pintype "unspecified+no_connect"))
    )
    (net (code "66") (name "unconnected-(U1-VBAT-Pad21)") (class "Default")
      (node (ref "U1") (pin "21") (pinfunction "VBAT_21") (pintype "unspecified+no_connect"))
    )
    (net (code "67") (name "unconnected-(U2-NC-Pad3)") (class "Default")
      (node (ref "U2") (pin "3") (pinfunction "NC_3") (pintype "unspecified+no_connect"))
    )
  )
)
